# USB-Charger-BMS.net
KiCad netlist of a schematic drawn in Altium Designer
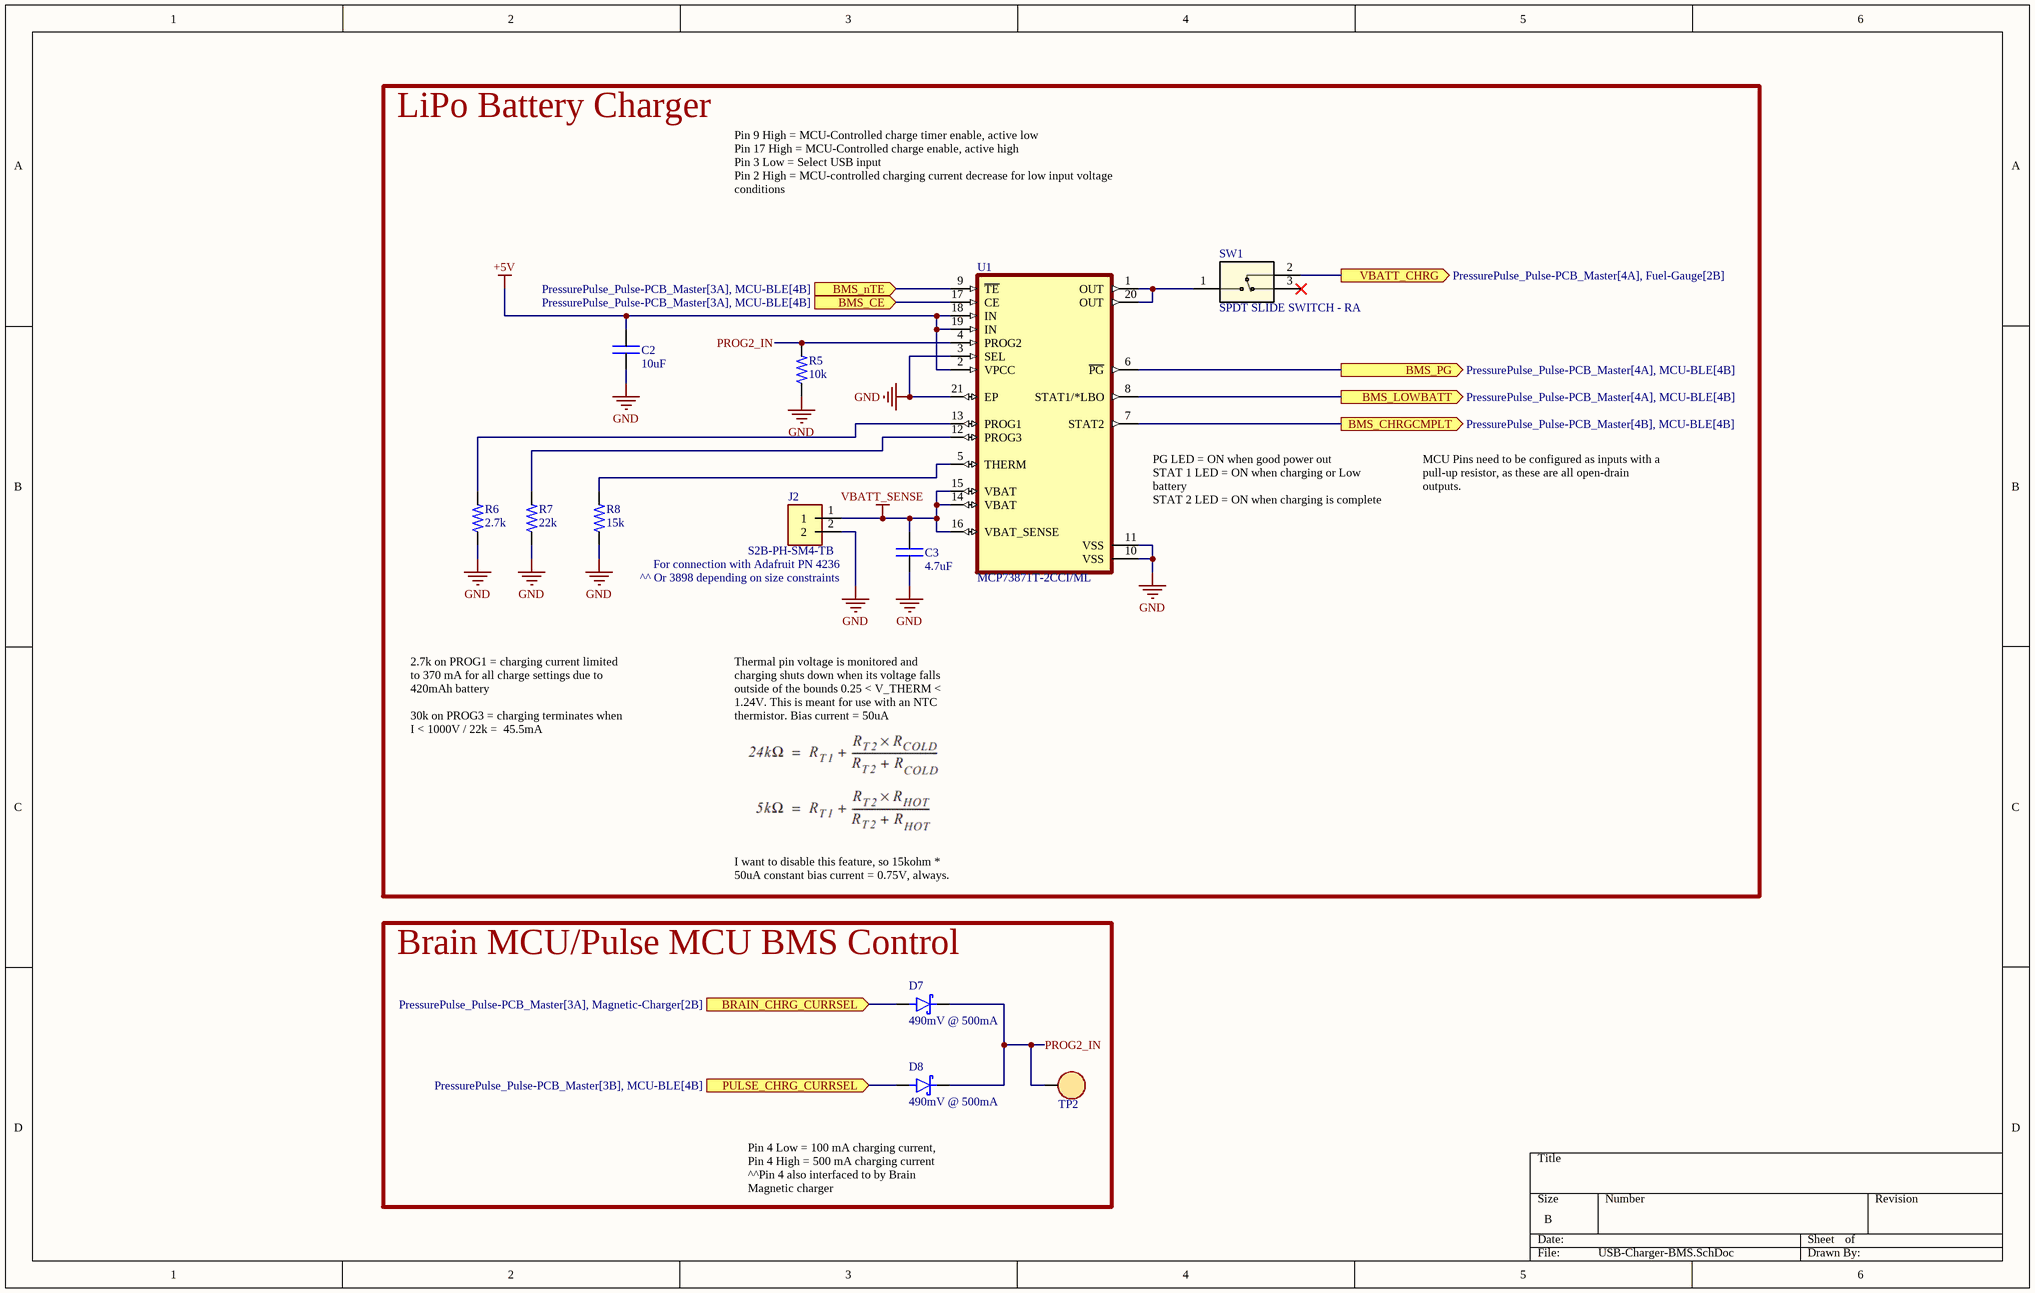
[diagram p0: USB-Charger-BMS.SchDoc]

(export (version "E")
  (design (tool "Eeschema 10.0.6"))
  (components
    (comp (ref "C2")
      (value "10uF")
      (footprint "PressurePulse:0402C")
      (description "Capacitor")
      (fields (field (name "Comment") "CAP"))
      (libsource (lib "PressurePulse") (part "CAP"))
    )
    (comp (ref "C3")
      (value "4.7uF")
      (footprint "PressurePulse:0402C")
      (description "Capacitor")
      (fields (field (name "Comment") "CAP"))
      (libsource (lib "PressurePulse") (part "CAP"))
    )
    (comp (ref "D7")
      (value "490mV @ 500mA")
      (footprint "PressurePulse:SOD-523")
      (fields (field (name "MFR") "Shikues"))
      (libsource (lib "PressurePulse") (part "SCHOTTKY DIODE"))
    )
    (comp (ref "D8")
      (value "490mV @ 500mA")
      (footprint "PressurePulse:SOD-523")
      (fields (field (name "MFR") "Shikues"))
      (libsource (lib "PressurePulse") (part "SCHOTTKY DIODE"))
    )
    (comp (ref "J2")
      (value "S2B-PH-SM4-TB")
      (footprint "PressurePulse:JST_PH-2POS-SMT-RA")
      (description "Connector Header Surface Mount, Right Angle 2 position 0.079 (2.00mm)")
      (fields (field (name "MFR") "JST Sales"))
      (libsource (lib "PressurePulse") (part "JST CONN 2POS PH"))
    )
    (comp (ref "R5")
      (value "10k")
      (footprint "PressurePulse:0402R")
      (description "Resistor")
      (fields (field (name "Comment") "RES"))
      (libsource (lib "PressurePulse") (part "RES"))
    )
    (comp (ref "R6")
      (value "2.7k")
      (footprint "PressurePulse:0402R")
      (description "Resistor")
      (fields (field (name "Comment") "RES"))
      (libsource (lib "PressurePulse") (part "RES"))
    )
    (comp (ref "R7")
      (value "22k")
      (footprint "PressurePulse:0402R")
      (description "Resistor")
      (fields (field (name "Comment") "RES"))
      (libsource (lib "PressurePulse") (part "RES"))
    )
    (comp (ref "R8")
      (value "15k")
      (footprint "PressurePulse:0402R")
      (description "Resistor")
      (fields (field (name "Comment") "RES"))
      (libsource (lib "PressurePulse") (part "RES"))
    )
    (comp (ref "SW1")
      (value "SPDT SLIDE SWITCH - RA")
      (footprint "PressurePulse:K3-1290S-J1")
      (fields (field (name "MFR") "Korean Hroparts Elec"))
      (libsource (lib "PressurePulse") (part "SPDT SLIDE SWITCH - RA"))
    )
    (comp (ref "TP2")
      (value "RH-5019")
      (footprint "PressurePulse:TP - RH-5019")
      (fields (field (name "MFR") "ronghe"))
      (libsource (lib "PressurePulse") (part "TEST POINT"))
    )
    (comp (ref "U1")
      (value "MCP73871T-2CCI/ML")
      (footprint "PressurePulse:20-VFQFN EXPOSED PAD")
      (description "Charger IC Lithium Ion/Polymer 20-QFN (4x4)")
      (fields (field (name "MFR") "Microchip Technology"))
      (libsource (lib "PressurePulse") (part "LiPo Batt Charger - Shared load"))
    )
  )
  (nets
    (net (code "1") (name "+5V") (class "Default")
      (node (ref "C2") (pin "2") (pinfunction "2_2") (pintype "passive"))
      (node (ref "U1") (pin "18") (pinfunction "IN_18") (pintype "input"))
      (node (ref "U1") (pin "19") (pinfunction "IN_19") (pintype "input"))
      (node (ref "U1") (pin "2") (pinfunction "VPCC_2") (pintype "input"))
    )
    (net (code "2") (name "/BMS_CE") (class "Default")
      (node (ref "U1") (pin "17") (pinfunction "CE_17") (pintype "input"))
    )
    (net (code "3") (name "/BMS_CHRGCMPLT") (class "Default")
      (node (ref "U1") (pin "7") (pinfunction "STAT2_7") (pintype "output"))
    )
    (net (code "4") (name "/BMS_LOWBATT") (class "Default")
      (node (ref "U1") (pin "8") (pinfunction "STAT1/*LBO_8") (pintype "output"))
    )
    (net (code "5") (name "/BMS_PG") (class "Default")
      (node (ref "U1") (pin "6") (pinfunction "~{PG}_6") (pintype "output"))
    )
    (net (code "6") (name "/BMS_nTE") (class "Default")
      (node (ref "U1") (pin "9") (pinfunction "~{TE}_9") (pintype "input"))
    )
    (net (code "7") (name "/BRAIN_CHRG_CURRSEL") (class "Default")
      (node (ref "D7") (pin "A") (pinfunction "A_A") (pintype "passive"))
    )
    (net (code "8") (name "/PROG2_IN") (class "Default")
      (node (ref "D7") (pin "K") (pinfunction "K_K") (pintype "passive"))
      (node (ref "D8") (pin "K") (pinfunction "K_K") (pintype "passive"))
      (node (ref "R5") (pin "2") (pinfunction "2_2") (pintype "passive"))
      (node (ref "TP2") (pin "1") (pinfunction "1_1") (pintype "passive"))
      (node (ref "U1") (pin "4") (pinfunction "PROG2_4") (pintype "input"))
    )
    (net (code "9") (name "/PULSE_CHRG_CURRSEL") (class "Default")
      (node (ref "D8") (pin "A") (pinfunction "A_A") (pintype "passive"))
    )
    (net (code "10") (name "/VBATT_CHRG") (class "Default")
      (node (ref "SW1") (pin "2") (pinfunction "2_2") (pintype "passive"))
    )
    (net (code "11") (name "GND") (class "Default")
      (node (ref "C2") (pin "1") (pinfunction "1_1") (pintype "passive"))
      (node (ref "C3") (pin "1") (pinfunction "1_1") (pintype "passive"))
      (node (ref "J2") (pin "2") (pinfunction "2_2") (pintype "passive"))
      (node (ref "R5") (pin "1") (pinfunction "1_1") (pintype "passive"))
      (node (ref "R6") (pin "1") (pinfunction "1_1") (pintype "passive"))
      (node (ref "R7") (pin "1") (pinfunction "1_1") (pintype "passive"))
      (node (ref "R8") (pin "1") (pinfunction "1_1") (pintype "passive"))
      (node (ref "U1") (pin "10") (pinfunction "VSS_10") (pintype "power_in"))
      (node (ref "U1") (pin "11") (pinfunction "VSS_11") (pintype "power_in"))
      (node (ref "U1") (pin "21") (pinfunction "EP_21") (pintype "bidirectional"))
      (node (ref "U1") (pin "3") (pinfunction "SEL_3") (pintype "input"))
    )
    (net (code "12") (name "Net-(SW1-Pad1)") (class "Default")
      (node (ref "SW1") (pin "1") (pinfunction "1_1") (pintype "passive"))
      (node (ref "U1") (pin "1") (pinfunction "OUT_1") (pintype "output"))
      (node (ref "U1") (pin "20") (pinfunction "OUT_20") (pintype "output"))
    )
    (net (code "13") (name "Net-(U1-PROG1)") (class "Default")
      (node (ref "R6") (pin "2") (pinfunction "2_2") (pintype "passive"))
      (node (ref "U1") (pin "13") (pinfunction "PROG1_13") (pintype "bidirectional"))
    )
    (net (code "14") (name "Net-(U1-PROG3)") (class "Default")
      (node (ref "R7") (pin "2") (pinfunction "2_2") (pintype "passive"))
      (node (ref "U1") (pin "12") (pinfunction "PROG3_12") (pintype "bidirectional"))
    )
    (net (code "15") (name "Net-(U1-THERM)") (class "Default")
      (node (ref "R8") (pin "2") (pinfunction "2_2") (pintype "passive"))
      (node (ref "U1") (pin "5") (pinfunction "THERM_5") (pintype "bidirectional"))
    )
    (net (code "16") (name "VBATT_SENSE") (class "Default")
      (node (ref "C3") (pin "2") (pinfunction "2_2") (pintype "passive"))
      (node (ref "J2") (pin "1") (pinfunction "1_1") (pintype "passive"))
      (node (ref "U1") (pin "14") (pinfunction "VBAT_14") (pintype "bidirectional"))
      (node (ref "U1") (pin "15") (pinfunction "VBAT_15") (pintype "bidirectional"))
      (node (ref "U1") (pin "16") (pinfunction "VBAT_SENSE_16") (pintype "bidirectional"))
    )
    (net (code "17") (name "unconnected-(SW1-Pad3)") (class "Default")
      (node (ref "SW1") (pin "3") (pinfunction "3_3") (pintype "passive+no_connect"))
    )
  )
)
